# Dual_Motor_Driver.net
KiCad netlist of a schematic drawn in EAGLE
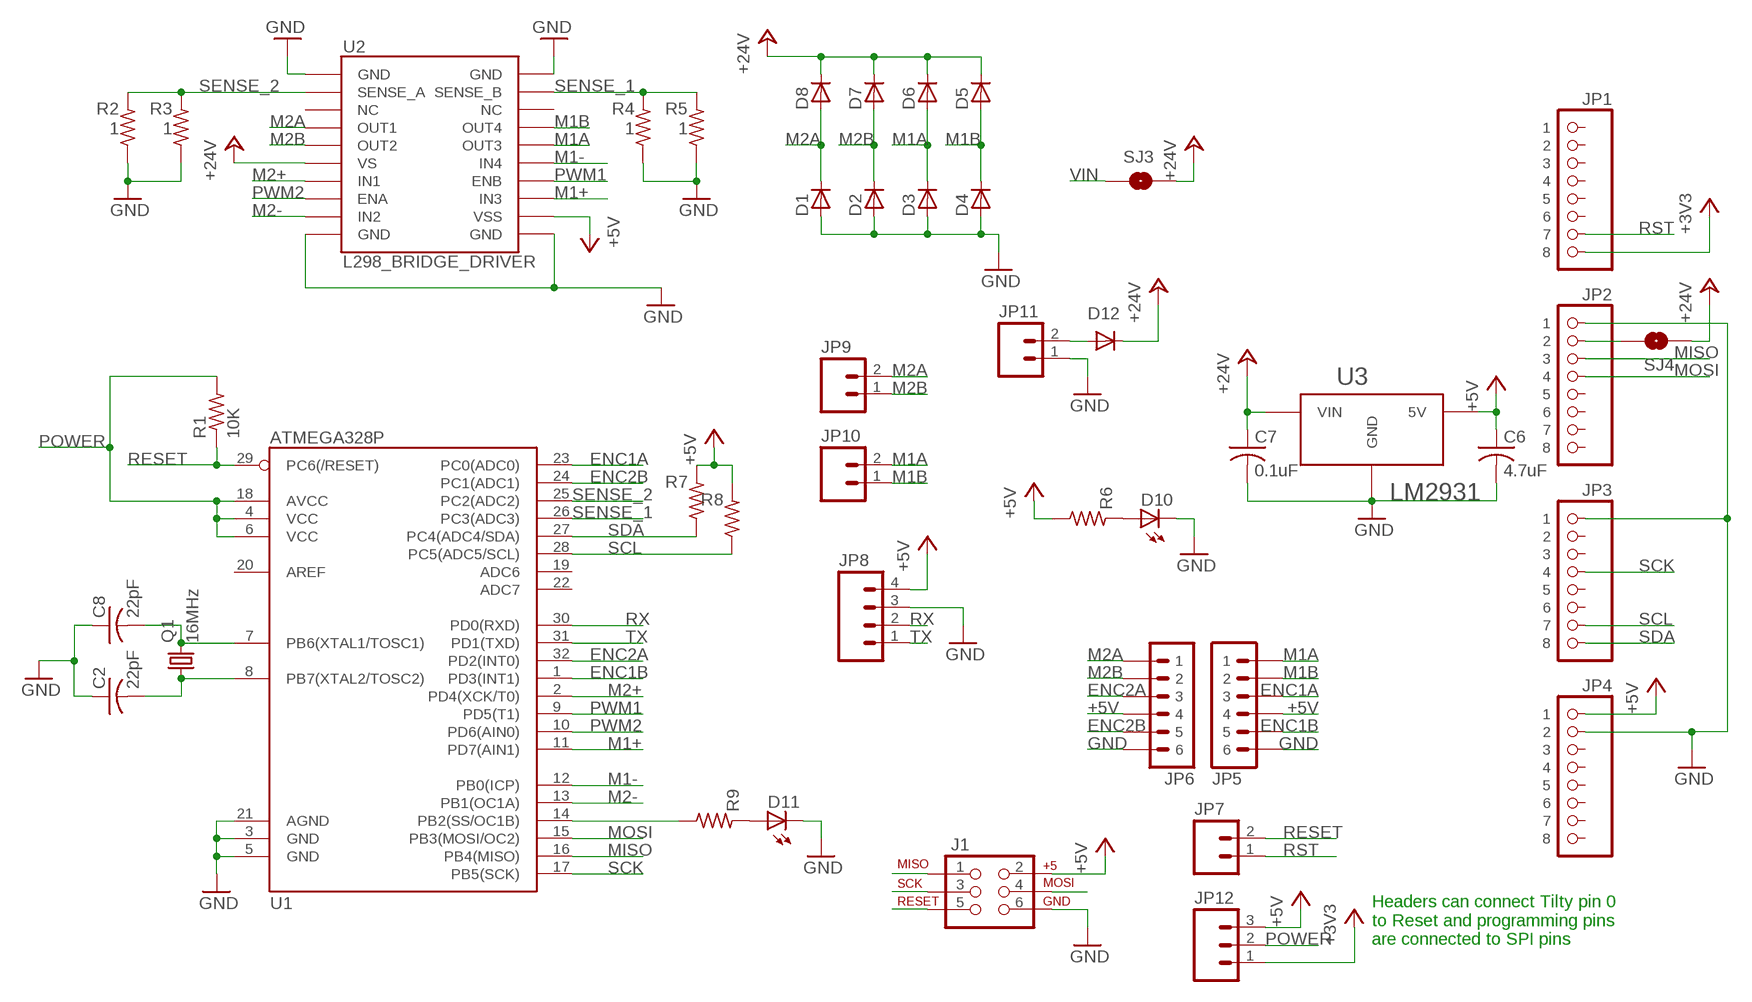
[diagram p0: schematic, sheet 1]

(export (version "E")
  (design (tool "Eeschema 10.0.6"))
  (components
    (comp (ref "C2")
      (value "22pF")
      (footprint "eagle-import:C0603")
      (libsource (lib "eagle-import") (part "C-USC0603"))
    )
    (comp (ref "C6")
      (value "4.7uF")
      (footprint "eagle-import:C0603")
      (libsource (lib "eagle-import") (part "C-USC0603"))
    )
    (comp (ref "C7")
      (value "0.1uF")
      (footprint "eagle-import:C0603")
      (libsource (lib "eagle-import") (part "C-USC0603"))
    )
    (comp (ref "C8")
      (value "22pF")
      (footprint "eagle-import:C0603")
      (libsource (lib "eagle-import") (part "C-USC0603"))
    )
    (comp (ref "D1")
      (value "D-SOD123")
      (footprint "eagle-import:SOD123")
      (fields (field (name "PART#") "CDBW140-G"))
      (libsource (lib "eagle-import") (part "D-SOD123"))
    )
    (comp (ref "D2")
      (value "D-SOD123")
      (footprint "eagle-import:SOD123")
      (fields (field (name "PART#") "CDBW140-G"))
      (libsource (lib "eagle-import") (part "D-SOD123"))
    )
    (comp (ref "D3")
      (value "D-SOD123")
      (footprint "eagle-import:SOD123")
      (fields (field (name "PART#") "CDBW140-G"))
      (libsource (lib "eagle-import") (part "D-SOD123"))
    )
    (comp (ref "D4")
      (value "D-SOD123")
      (footprint "eagle-import:SOD123")
      (fields (field (name "PART#") "CDBW140-G"))
      (libsource (lib "eagle-import") (part "D-SOD123"))
    )
    (comp (ref "D5")
      (value "D-SOD123")
      (footprint "eagle-import:SOD123")
      (fields (field (name "PART#") "CDBW140-G"))
      (libsource (lib "eagle-import") (part "D-SOD123"))
    )
    (comp (ref "D6")
      (value "D-SOD123")
      (footprint "eagle-import:SOD123")
      (fields (field (name "PART#") "CDBW140-G"))
      (libsource (lib "eagle-import") (part "D-SOD123"))
    )
    (comp (ref "D7")
      (value "D-SOD123")
      (footprint "eagle-import:SOD123")
      (fields (field (name "PART#") "CDBW140-G"))
      (libsource (lib "eagle-import") (part "D-SOD123"))
    )
    (comp (ref "D8")
      (value "D-SOD123")
      (footprint "eagle-import:SOD123")
      (fields (field (name "PART#") "CDBW140-G"))
      (libsource (lib "eagle-import") (part "D-SOD123"))
    )
    (comp (ref "D10")
      (value "LED-GREENLED-0805_NO_SILK")
      (footprint "eagle-import:LED-0805")
      (libsource (lib "eagle-import") (part "LED-GREENLED-0805_NO_SILK"))
    )
    (comp (ref "D11")
      (value "LED-GREENLED-0805_NO_SILK")
      (footprint "eagle-import:LED-0805")
      (libsource (lib "eagle-import") (part "LED-GREENLED-0805_NO_SILK"))
    )
    (comp (ref "D12")
      (value "DIODESMB")
      (footprint "eagle-import:SMB-DIODE")
      (libsource (lib "eagle-import") (part "DIODESMB"))
    )
    (comp (ref "J1")
      (value "AVR_SPI_PRG_62X3_LOCK")
      (footprint "eagle-import:2X3_LOCK")
      (libsource (lib "eagle-import") (part "AVR_SPI_PRG_62X3_LOCK"))
    )
    (comp (ref "JP1")
      (value "8-PIN_HEADER")
      (footprint "eagle-import:8-PIN_RECEPTACLE_LOCK_NO-SS")
      (libsource (lib "eagle-import") (part "8-PIN_HEADER"))
    )
    (comp (ref "JP2")
      (value "8-PIN_HEADER")
      (footprint "eagle-import:8-PIN_RECEPTACLE_LOCK_NO-SS")
      (libsource (lib "eagle-import") (part "8-PIN_HEADER"))
    )
    (comp (ref "JP3")
      (value "8-PIN_HEADER")
      (footprint "eagle-import:8-PIN_RECEPTACLE_LOCK_NO-SS")
      (libsource (lib "eagle-import") (part "8-PIN_HEADER"))
    )
    (comp (ref "JP4")
      (value "8-PIN_HEADER")
      (footprint "eagle-import:8-PIN_RECEPTACLE_LOCK_NO-SS")
      (libsource (lib "eagle-import") (part "8-PIN_HEADER"))
    )
    (comp (ref "JP5")
      (value "6PIN-SH_RIGHT_ANGLE")
      (footprint "eagle-import:6PIN-SH_SERIES_RA")
      (fields (field (name "PART#") "SM06B-SRSS-TB(LF)(SN)"))
      (libsource (lib "eagle-import") (part "6PIN-SH_RIGHT_ANGLE"))
    )
    (comp (ref "JP6")
      (value "6PIN-SH_RIGHT_ANGLE")
      (footprint "eagle-import:6PIN-SH_SERIES_RA")
      (fields (field (name "PART#") "SM06B-SRSS-TB(LF)(SN)"))
      (libsource (lib "eagle-import") (part "6PIN-SH_RIGHT_ANGLE"))
    )
    (comp (ref "JP7")
      (value "M02PTH")
      (footprint "eagle-import:1X02")
      (libsource (lib "eagle-import") (part "M02PTH"))
    )
    (comp (ref "JP8")
      (value "M04PTH")
      (footprint "eagle-import:1X04")
      (libsource (lib "eagle-import") (part "M04PTH"))
    )
    (comp (ref "JP9")
      (value "M02PTH")
      (footprint "eagle-import:1X02")
      (libsource (lib "eagle-import") (part "M02PTH"))
    )
    (comp (ref "JP10")
      (value "M02PTH")
      (footprint "eagle-import:1X02")
      (libsource (lib "eagle-import") (part "M02PTH"))
    )
    (comp (ref "JP11")
      (value "M02PTH")
      (footprint "eagle-import:1X02")
      (libsource (lib "eagle-import") (part "M02PTH"))
    )
    (comp (ref "JP12")
      (value "M03PTH")
      (footprint "eagle-import:1X03")
      (libsource (lib "eagle-import") (part "M03PTH"))
    )
    (comp (ref "Q1")
      (value "16MHz")
      (footprint "eagle-import:CTS406")
      (fields (field (name "PART#") "406C35D16M00000"))
      (libsource (lib "eagle-import") (part "CRYSTALCTS406"))
    )
    (comp (ref "R1")
      (value "10K")
      (footprint "eagle-import:R0603")
      (libsource (lib "eagle-import") (part "R-US_R0603"))
    )
    (comp (ref "R2")
      (value "1")
      (footprint "eagle-import:R0603")
      (libsource (lib "eagle-import") (part "R-US_R0603"))
    )
    (comp (ref "R3")
      (value "1")
      (footprint "eagle-import:R0603")
      (libsource (lib "eagle-import") (part "R-US_R0603"))
    )
    (comp (ref "R4")
      (value "1")
      (footprint "eagle-import:R0603")
      (libsource (lib "eagle-import") (part "R-US_R0603"))
    )
    (comp (ref "R5")
      (value "1")
      (footprint "eagle-import:R0603")
      (libsource (lib "eagle-import") (part "R-US_R0603"))
    )
    (comp (ref "R6")
      (value "R-US_R0603")
      (footprint "eagle-import:R0603")
      (libsource (lib "eagle-import") (part "R-US_R0603"))
    )
    (comp (ref "R7")
      (value "R-US_R0603")
      (footprint "eagle-import:R0603")
      (libsource (lib "eagle-import") (part "R-US_R0603"))
    )
    (comp (ref "R8")
      (value "R-US_R0603")
      (footprint "eagle-import:R0603")
      (libsource (lib "eagle-import") (part "R-US_R0603"))
    )
    (comp (ref "R9")
      (value "R-US_R0603")
      (footprint "eagle-import:R0603")
      (libsource (lib "eagle-import") (part "R-US_R0603"))
    )
    (comp (ref "SJ3")
      (value "SOLDERJUMPERNC")
      (footprint "eagle-import:SJ_2S")
      (libsource (lib "eagle-import") (part "SOLDERJUMPERNC"))
    )
    (comp (ref "SJ4")
      (value "SOLDERJUMPERTRACE")
      (footprint "eagle-import:SJ_2S-TRACE")
      (libsource (lib "eagle-import") (part "SOLDERJUMPERTRACE"))
    )
    (comp (ref "U1")
      (value "ATMEGA328P")
      (footprint "eagle-import:TQFP32-08")
      (libsource (lib "eagle-import") (part "ATMEGA328_SMT"))
    )
    (comp (ref "U2")
      (value "L298_BRIDGE_DRIVER")
      (footprint "eagle-import:POWERSO20")
      (libsource (lib "eagle-import") (part "L298_BRIDGE_DRIVER"))
    )
    (comp (ref "U3")
      (value "LM2931")
      (footprint "eagle-import:TO263")
      (libsource (lib "eagle-import") (part "LM2931"))
    )
  )
  (nets
    (net (code "1") (name "+3V3") (class "Default")
      (node (ref "JP1") (pin "P$8") (pinfunction "8_P$8") (pintype "passive"))
      (node (ref "JP12") (pin "1") (pinfunction "1_1") (pintype "passive"))
    )
    (net (code "2") (name "+5V") (class "Default")
      (node (ref "C6") (pin "1") (pinfunction "1_1") (pintype "passive"))
      (node (ref "J1") (pin "2") (pinfunction "2_2") (pintype "passive"))
      (node (ref "JP12") (pin "3") (pinfunction "3_3") (pintype "passive"))
      (node (ref "JP4") (pin "P$1") (pinfunction "1_P$1") (pintype "passive"))
      (node (ref "JP5") (pin "P$4") (pinfunction "4_P$4") (pintype "passive"))
      (node (ref "JP6") (pin "P$4") (pinfunction "4_P$4") (pintype "passive"))
      (node (ref "JP8") (pin "4") (pinfunction "4_4") (pintype "passive"))
      (node (ref "R6") (pin "1") (pinfunction "1_1") (pintype "passive"))
      (node (ref "R7") (pin "2") (pinfunction "2_2") (pintype "passive"))
      (node (ref "R8") (pin "2") (pinfunction "2_2") (pintype "passive"))
      (node (ref "U2") (pin "12") (pinfunction "VSS_12") (pintype "bidirectional"))
      (node (ref "U3") (pin "P$3") (pinfunction "5V_P$3") (pintype "bidirectional"))
    )
    (net (code "3") (name "+24V") (class "Default")
      (node (ref "C7") (pin "1") (pinfunction "1_1") (pintype "passive"))
      (node (ref "D12") (pin "C") (pinfunction "C_C") (pintype "passive"))
      (node (ref "D5") (pin "1") (pinfunction "C_1") (pintype "passive"))
      (node (ref "D6") (pin "1") (pinfunction "C_1") (pintype "passive"))
      (node (ref "D7") (pin "1") (pinfunction "C_1") (pintype "passive"))
      (node (ref "D8") (pin "1") (pinfunction "C_1") (pintype "passive"))
      (node (ref "SJ3") (pin "2") (pinfunction "2_2") (pintype "passive"))
      (node (ref "SJ4") (pin "1") (pinfunction "1_1") (pintype "passive"))
      (node (ref "U2") (pin "6") (pinfunction "VS_6") (pintype "bidirectional"))
      (node (ref "U3") (pin "P$2") (pinfunction "VIN_P$2") (pintype "bidirectional"))
    )
    (net (code "4") (name "/ENC1A") (class "Default")
      (node (ref "JP5") (pin "P$3") (pinfunction "3_P$3") (pintype "passive"))
      (node (ref "U1") (pin "23") (pinfunction "PC0(ADC0)_23") (pintype "bidirectional"))
    )
    (net (code "5") (name "/ENC1B") (class "Default")
      (node (ref "JP5") (pin "P$5") (pinfunction "5_P$5") (pintype "passive"))
      (node (ref "U1") (pin "1") (pinfunction "PD3(INT1)_1") (pintype "bidirectional"))
    )
    (net (code "6") (name "/ENC2A") (class "Default")
      (node (ref "JP6") (pin "P$3") (pinfunction "3_P$3") (pintype "passive"))
      (node (ref "U1") (pin "32") (pinfunction "PD2(INT0)_32") (pintype "bidirectional"))
    )
    (net (code "7") (name "/ENC2B") (class "Default")
      (node (ref "JP6") (pin "P$5") (pinfunction "5_P$5") (pintype "passive"))
      (node (ref "U1") (pin "24") (pinfunction "PC1(ADC1)_24") (pintype "bidirectional"))
    )
    (net (code "8") (name "/M1+") (class "Default")
      (node (ref "U1") (pin "11") (pinfunction "PD7(AIN1)_11") (pintype "bidirectional"))
      (node (ref "U2") (pin "13") (pinfunction "IN3_13") (pintype "bidirectional"))
    )
    (net (code "9") (name "/M1-") (class "Default")
      (node (ref "U1") (pin "12") (pinfunction "PB0(ICP)_12") (pintype "bidirectional"))
      (node (ref "U2") (pin "15") (pinfunction "IN4_15") (pintype "bidirectional"))
    )
    (net (code "10") (name "/M1A") (class "Default")
      (node (ref "D3") (pin "1") (pinfunction "C_1") (pintype "passive"))
      (node (ref "D6") (pin "2") (pinfunction "A_2") (pintype "passive"))
      (node (ref "JP10") (pin "2") (pinfunction "2_2") (pintype "passive"))
      (node (ref "JP5") (pin "P$1") (pinfunction "1_P$1") (pintype "passive"))
      (node (ref "U2") (pin "16") (pinfunction "OUT3_16") (pintype "bidirectional"))
    )
    (net (code "11") (name "/M1B") (class "Default")
      (node (ref "D4") (pin "1") (pinfunction "C_1") (pintype "passive"))
      (node (ref "D5") (pin "2") (pinfunction "A_2") (pintype "passive"))
      (node (ref "JP10") (pin "1") (pinfunction "1_1") (pintype "passive"))
      (node (ref "JP5") (pin "P$2") (pinfunction "2_P$2") (pintype "passive"))
      (node (ref "U2") (pin "17") (pinfunction "OUT4_17") (pintype "bidirectional"))
    )
    (net (code "12") (name "/M2+") (class "Default")
      (node (ref "U1") (pin "2") (pinfunction "PD4(XCK/T0)_2") (pintype "bidirectional"))
      (node (ref "U2") (pin "7") (pinfunction "IN1_7") (pintype "bidirectional"))
    )
    (net (code "13") (name "/M2-") (class "Default")
      (node (ref "U1") (pin "13") (pinfunction "PB1(OC1A)_13") (pintype "bidirectional"))
      (node (ref "U2") (pin "9") (pinfunction "IN2_9") (pintype "bidirectional"))
    )
    (net (code "14") (name "/M2A") (class "Default")
      (node (ref "D1") (pin "1") (pinfunction "C_1") (pintype "passive"))
      (node (ref "D8") (pin "2") (pinfunction "A_2") (pintype "passive"))
      (node (ref "JP6") (pin "P$1") (pinfunction "1_P$1") (pintype "passive"))
      (node (ref "JP9") (pin "2") (pinfunction "2_2") (pintype "passive"))
      (node (ref "U2") (pin "4") (pinfunction "OUT1_4") (pintype "bidirectional"))
    )
    (net (code "15") (name "/M2B") (class "Default")
      (node (ref "D2") (pin "1") (pinfunction "C_1") (pintype "passive"))
      (node (ref "D7") (pin "2") (pinfunction "A_2") (pintype "passive"))
      (node (ref "JP6") (pin "P$2") (pinfunction "2_P$2") (pintype "passive"))
      (node (ref "JP9") (pin "1") (pinfunction "1_1") (pintype "passive"))
      (node (ref "U2") (pin "5") (pinfunction "OUT2_5") (pintype "bidirectional"))
    )
    (net (code "16") (name "/MISO") (class "Default")
      (node (ref "J1") (pin "1") (pinfunction "1_1") (pintype "passive"))
      (node (ref "JP2") (pin "P$3") (pinfunction "3_P$3") (pintype "passive"))
      (node (ref "U1") (pin "16") (pinfunction "PB4(MISO)_16") (pintype "bidirectional"))
    )
    (net (code "17") (name "/MOSI") (class "Default")
      (node (ref "J1") (pin "4") (pinfunction "4_4") (pintype "passive"))
      (node (ref "JP2") (pin "P$4") (pinfunction "4_P$4") (pintype "passive"))
      (node (ref "U1") (pin "15") (pinfunction "PB3(MOSI/OC2)_15") (pintype "bidirectional"))
    )
    (net (code "18") (name "/POWER") (class "Default")
      (node (ref "JP12") (pin "2") (pinfunction "2_2") (pintype "passive"))
      (node (ref "R1") (pin "2") (pinfunction "2_2") (pintype "passive"))
      (node (ref "U1") (pin "18") (pinfunction "AVCC_18") (pintype "bidirectional"))
      (node (ref "U1") (pin "4") (pinfunction "VCC_4") (pintype "bidirectional"))
      (node (ref "U1") (pin "6") (pinfunction "VCC_6") (pintype "bidirectional"))
    )
    (net (code "19") (name "/PWM1") (class "Default")
      (node (ref "U1") (pin "9") (pinfunction "PD5(T1)_9") (pintype "bidirectional"))
      (node (ref "U2") (pin "14") (pinfunction "ENB_14") (pintype "bidirectional"))
    )
    (net (code "20") (name "/PWM2") (class "Default")
      (node (ref "U1") (pin "10") (pinfunction "PD6(AIN0)_10") (pintype "bidirectional"))
      (node (ref "U2") (pin "8") (pinfunction "ENA_8") (pintype "bidirectional"))
    )
    (net (code "21") (name "/RESET") (class "Default")
      (node (ref "J1") (pin "5") (pinfunction "5_5") (pintype "passive"))
      (node (ref "JP7") (pin "2") (pinfunction "2_2") (pintype "passive"))
      (node (ref "R1") (pin "1") (pinfunction "1_1") (pintype "passive"))
      (node (ref "U1") (pin "29") (pinfunction "PC6(/RESET)_29") (pintype "bidirectional"))
    )
    (net (code "22") (name "/RST") (class "Default")
      (node (ref "JP1") (pin "P$7") (pinfunction "7_P$7") (pintype "passive"))
      (node (ref "JP7") (pin "1") (pinfunction "1_1") (pintype "passive"))
    )
    (net (code "23") (name "/RX") (class "Default")
      (node (ref "JP8") (pin "2") (pinfunction "2_2") (pintype "passive"))
      (node (ref "U1") (pin "30") (pinfunction "PD0(RXD)_30") (pintype "bidirectional"))
    )
    (net (code "24") (name "/SCK") (class "Default")
      (node (ref "J1") (pin "3") (pinfunction "3_3") (pintype "passive"))
      (node (ref "JP3") (pin "P$4") (pinfunction "4_P$4") (pintype "passive"))
      (node (ref "U1") (pin "17") (pinfunction "PB5(SCK)_17") (pintype "bidirectional"))
    )
    (net (code "25") (name "/SCL") (class "Default")
      (node (ref "JP3") (pin "P$7") (pinfunction "7_P$7") (pintype "passive"))
      (node (ref "R8") (pin "1") (pinfunction "1_1") (pintype "passive"))
      (node (ref "U1") (pin "28") (pinfunction "PC5(ADC5/SCL)_28") (pintype "bidirectional"))
    )
    (net (code "26") (name "/SDA") (class "Default")
      (node (ref "JP3") (pin "P$8") (pinfunction "8_P$8") (pintype "passive"))
      (node (ref "R7") (pin "1") (pinfunction "1_1") (pintype "passive"))
      (node (ref "U1") (pin "27") (pinfunction "PC4(ADC4/SDA)_27") (pintype "bidirectional"))
    )
    (net (code "27") (name "/SENSE_1") (class "Default")
      (node (ref "R4") (pin "2") (pinfunction "2_2") (pintype "passive"))
      (node (ref "R5") (pin "2") (pinfunction "2_2") (pintype "passive"))
      (node (ref "U1") (pin "26") (pinfunction "PC3(ADC3)_26") (pintype "bidirectional"))
      (node (ref "U2") (pin "19") (pinfunction "SENSE_B_19") (pintype "bidirectional"))
    )
    (net (code "28") (name "/SENSE_2") (class "Default")
      (node (ref "R2") (pin "2") (pinfunction "2_2") (pintype "passive"))
      (node (ref "R3") (pin "2") (pinfunction "2_2") (pintype "passive"))
      (node (ref "U1") (pin "25") (pinfunction "PC2(ADC2)_25") (pintype "bidirectional"))
      (node (ref "U2") (pin "2") (pinfunction "SENSE_A_2") (pintype "bidirectional"))
    )
    (net (code "29") (name "/TX") (class "Default")
      (node (ref "JP8") (pin "1") (pinfunction "1_1") (pintype "passive"))
      (node (ref "U1") (pin "31") (pinfunction "PD1(TXD)_31") (pintype "bidirectional"))
    )
    (net (code "30") (name "/VIN") (class "Default")
      (node (ref "D12") (pin "A") (pinfunction "A_A") (pintype "passive"))
      (node (ref "JP11") (pin "2") (pinfunction "2_2") (pintype "passive"))
      (node (ref "SJ3") (pin "1") (pinfunction "1_1") (pintype "passive"))
    )
    (net (code "31") (name "GND") (class "Default")
      (node (ref "C2") (pin "1") (pinfunction "1_1") (pintype "passive"))
      (node (ref "C6") (pin "2") (pinfunction "2_2") (pintype "passive"))
      (node (ref "C7") (pin "2") (pinfunction "2_2") (pintype "passive"))
      (node (ref "C8") (pin "1") (pinfunction "1_1") (pintype "passive"))
      (node (ref "D1") (pin "2") (pinfunction "A_2") (pintype "passive"))
      (node (ref "D10") (pin "2") (pinfunction "C_2") (pintype "passive"))
      (node (ref "D11") (pin "2") (pinfunction "C_2") (pintype "passive"))
      (node (ref "D2") (pin "2") (pinfunction "A_2") (pintype "passive"))
      (node (ref "D3") (pin "2") (pinfunction "A_2") (pintype "passive"))
      (node (ref "D4") (pin "2") (pinfunction "A_2") (pintype "passive"))
      (node (ref "J1") (pin "6") (pinfunction "6_6") (pintype "passive"))
      (node (ref "JP11") (pin "1") (pinfunction "1_1") (pintype "passive"))
      (node (ref "JP2") (pin "P$1") (pinfunction "1_P$1") (pintype "passive"))
      (node (ref "JP3") (pin "P$1") (pinfunction "1_P$1") (pintype "passive"))
      (node (ref "JP4") (pin "P$2") (pinfunction "2_P$2") (pintype "passive"))
      (node (ref "JP5") (pin "P$6") (pinfunction "6_P$6") (pintype "passive"))
      (node (ref "JP6") (pin "P$6") (pinfunction "6_P$6") (pintype "passive"))
      (node (ref "JP8") (pin "3") (pinfunction "3_3") (pintype "passive"))
      (node (ref "R2") (pin "1") (pinfunction "1_1") (pintype "passive"))
      (node (ref "R3") (pin "1") (pinfunction "1_1") (pintype "passive"))
      (node (ref "R4") (pin "1") (pinfunction "1_1") (pintype "passive"))
      (node (ref "R5") (pin "1") (pinfunction "1_1") (pintype "passive"))
      (node (ref "U1") (pin "21") (pinfunction "AGND_21") (pintype "bidirectional"))
      (node (ref "U1") (pin "3") (pinfunction "GND_3") (pintype "bidirectional"))
      (node (ref "U1") (pin "5") (pinfunction "GND_5") (pintype "bidirectional"))
      (node (ref "U2") (pin "1") (pinfunction "GND_1") (pintype "bidirectional"))
      (node (ref "U2") (pin "10") (pinfunction "GND_10") (pintype "bidirectional"))
      (node (ref "U2") (pin "11") (pinfunction "GND_11") (pintype "bidirectional"))
      (node (ref "U2") (pin "20") (pinfunction "GND_20") (pintype "bidirectional"))
      (node (ref "U3") (pin "P$1") (pinfunction "GND_P$1") (pintype "bidirectional"))
    )
    (net (code "32") (name "Net-(D10-A)") (class "Default")
      (node (ref "D10") (pin "1") (pinfunction "A_1") (pintype "passive"))
      (node (ref "R6") (pin "2") (pinfunction "2_2") (pintype "passive"))
    )
    (net (code "33") (name "Net-(D11-A)") (class "Default")
      (node (ref "D11") (pin "1") (pinfunction "A_1") (pintype "passive"))
      (node (ref "R9") (pin "2") (pinfunction "2_2") (pintype "passive"))
    )
    (net (code "34") (name "Net-(JP2-2)") (class "Default")
      (node (ref "JP2") (pin "P$2") (pinfunction "2_P$2") (pintype "passive"))
      (node (ref "SJ4") (pin "2") (pinfunction "2_2") (pintype "passive"))
    )
    (net (code "35") (name "Net-(Q1-2)") (class "Default")
      (node (ref "C8") (pin "2") (pinfunction "2_2") (pintype "passive"))
      (node (ref "Q1") (pin "3") (pinfunction "2_3") (pintype "passive"))
      (node (ref "U1") (pin "7") (pinfunction "PB6(XTAL1/TOSC1)_7") (pintype "bidirectional"))
    )
    (net (code "36") (name "Net-(U1-PB2(SS{slash}OC1B))") (class "Default")
      (node (ref "R9") (pin "1") (pinfunction "1_1") (pintype "passive"))
      (node (ref "U1") (pin "14") (pinfunction "PB2(SS/OC1B)_14") (pintype "bidirectional"))
    )
    (net (code "37") (name "Net-(U1-PB7(XTAL2{slash}TOSC2))") (class "Default")
      (node (ref "C2") (pin "2") (pinfunction "2_2") (pintype "passive"))
      (node (ref "Q1") (pin "1") (pinfunction "1_1") (pintype "passive"))
      (node (ref "U1") (pin "8") (pinfunction "PB7(XTAL2/TOSC2)_8") (pintype "bidirectional"))
    )
    (net (code "38") (name "unconnected-(JP1-1-PadP$1)") (class "Default")
      (node (ref "JP1") (pin "P$1") (pinfunction "1_P$1") (pintype "passive"))
    )
    (net (code "39") (name "unconnected-(JP1-2-PadP$2)") (class "Default")
      (node (ref "JP1") (pin "P$2") (pinfunction "2_P$2") (pintype "passive"))
    )
    (net (code "40") (name "unconnected-(JP1-3-PadP$3)") (class "Default")
      (node (ref "JP1") (pin "P$3") (pinfunction "3_P$3") (pintype "passive"))
    )
    (net (code "41") (name "unconnected-(JP1-4-PadP$4)") (class "Default")
      (node (ref "JP1") (pin "P$4") (pinfunction "4_P$4") (pintype "passive"))
    )
    (net (code "42") (name "unconnected-(JP1-5-PadP$5)") (class "Default")
      (node (ref "JP1") (pin "P$5") (pinfunction "5_P$5") (pintype "passive"))
    )
    (net (code "43") (name "unconnected-(JP1-6-PadP$6)") (class "Default")
      (node (ref "JP1") (pin "P$6") (pinfunction "6_P$6") (pintype "passive"))
    )
    (net (code "44") (name "unconnected-(JP2-5-PadP$5)") (class "Default")
      (node (ref "JP2") (pin "P$5") (pinfunction "5_P$5") (pintype "passive"))
    )
    (net (code "45") (name "unconnected-(JP2-6-PadP$6)") (class "Default")
      (node (ref "JP2") (pin "P$6") (pinfunction "6_P$6") (pintype "passive"))
    )
    (net (code "46") (name "unconnected-(JP2-7-PadP$7)") (class "Default")
      (node (ref "JP2") (pin "P$7") (pinfunction "7_P$7") (pintype "passive"))
    )
    (net (code "47") (name "unconnected-(JP2-8-PadP$8)") (class "Default")
      (node (ref "JP2") (pin "P$8") (pinfunction "8_P$8") (pintype "passive"))
    )
    (net (code "48") (name "unconnected-(JP3-2-PadP$2)") (class "Default")
      (node (ref "JP3") (pin "P$2") (pinfunction "2_P$2") (pintype "passive"))
    )
    (net (code "49") (name "unconnected-(JP3-3-PadP$3)") (class "Default")
      (node (ref "JP3") (pin "P$3") (pinfunction "3_P$3") (pintype "passive"))
    )
    (net (code "50") (name "unconnected-(JP3-5-PadP$5)") (class "Default")
      (node (ref "JP3") (pin "P$5") (pinfunction "5_P$5") (pintype "passive"))
    )
    (net (code "51") (name "unconnected-(JP3-6-PadP$6)") (class "Default")
      (node (ref "JP3") (pin "P$6") (pinfunction "6_P$6") (pintype "passive"))
    )
    (net (code "52") (name "unconnected-(JP4-3-PadP$3)") (class "Default")
      (node (ref "JP4") (pin "P$3") (pinfunction "3_P$3") (pintype "passive"))
    )
    (net (code "53") (name "unconnected-(JP4-4-PadP$4)") (class "Default")
      (node (ref "JP4") (pin "P$4") (pinfunction "4_P$4") (pintype "passive"))
    )
    (net (code "54") (name "unconnected-(JP4-5-PadP$5)") (class "Default")
      (node (ref "JP4") (pin "P$5") (pinfunction "5_P$5") (pintype "passive"))
    )
    (net (code "55") (name "unconnected-(JP4-6-PadP$6)") (class "Default")
      (node (ref "JP4") (pin "P$6") (pinfunction "6_P$6") (pintype "passive"))
    )
    (net (code "56") (name "unconnected-(JP4-7-PadP$7)") (class "Default")
      (node (ref "JP4") (pin "P$7") (pinfunction "7_P$7") (pintype "passive"))
    )
    (net (code "57") (name "unconnected-(JP4-8-PadP$8)") (class "Default")
      (node (ref "JP4") (pin "P$8") (pinfunction "8_P$8") (pintype "passive"))
    )
    (net (code "58") (name "unconnected-(U1-ADC6-Pad19)") (class "Default")
      (node (ref "U1") (pin "19") (pinfunction "ADC6_19") (pintype "bidirectional"))
    )
    (net (code "59") (name "unconnected-(U1-ADC7-Pad22)") (class "Default")
      (node (ref "U1") (pin "22") (pinfunction "ADC7_22") (pintype "bidirectional"))
    )
    (net (code "60") (name "unconnected-(U1-AREF-Pad20)") (class "Default")
      (node (ref "U1") (pin "20") (pinfunction "AREF_20") (pintype "bidirectional"))
    )
    (net (code "61") (name "unconnected-(U2-NC-Pad3)") (class "Default")
      (node (ref "U2") (pin "3") (pinfunction "NC_3") (pintype "bidirectional"))
    )
    (net (code "62") (name "unconnected-(U2-NC-Pad18)") (class "Default")
      (node (ref "U2") (pin "18") (pinfunction "NC_18") (pintype "bidirectional"))
    )
  )
)
